# Jukebox.net
KiCad netlist of a schematic drawn in EAGLE
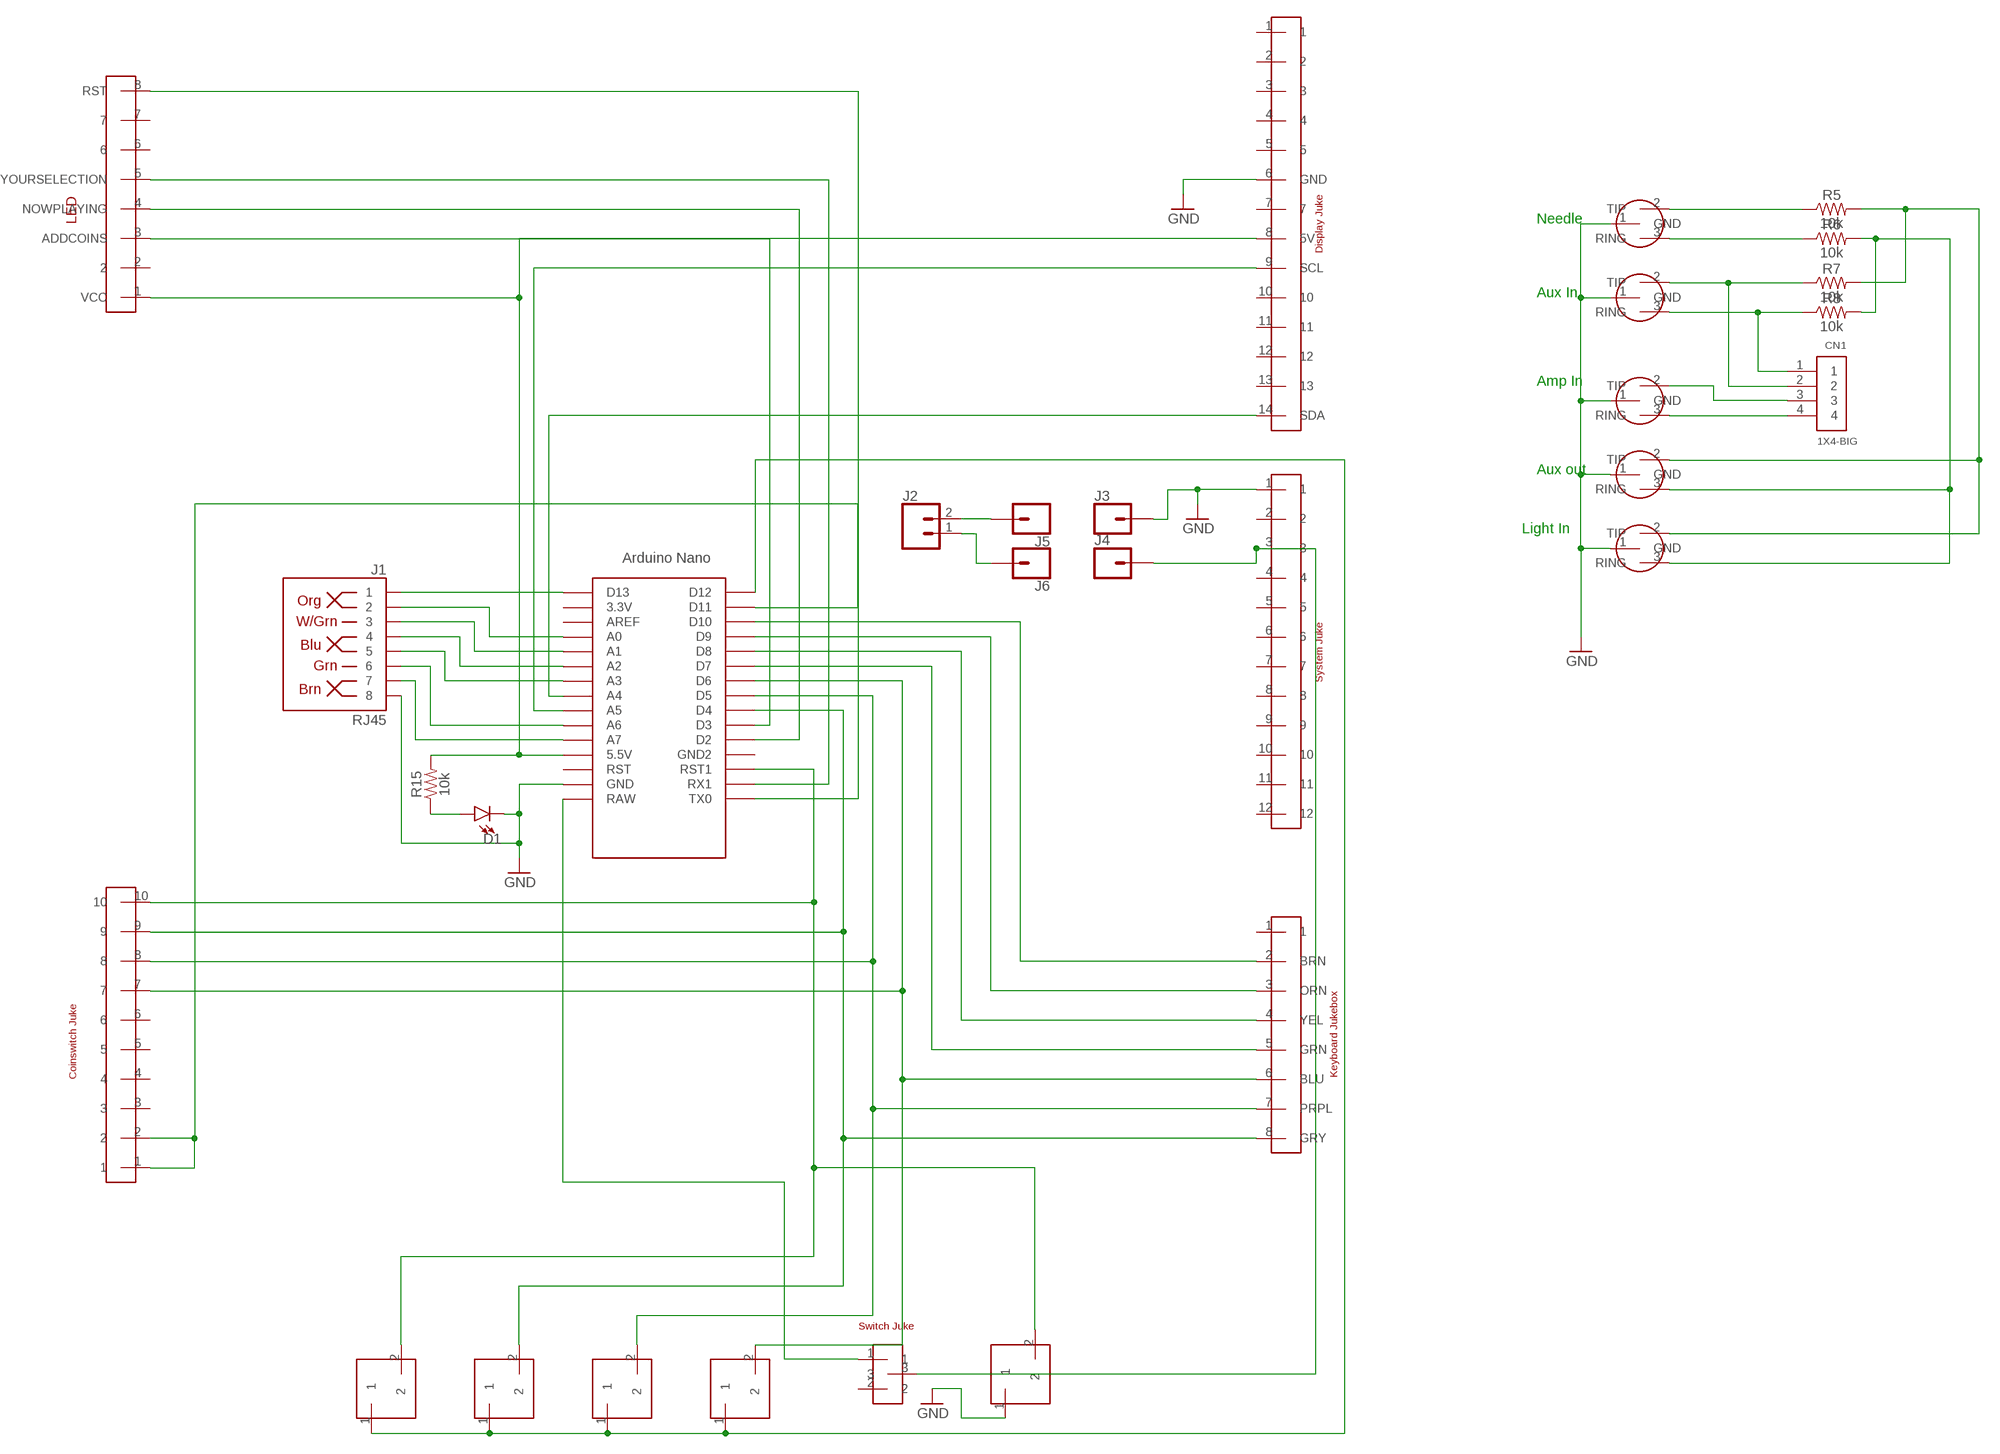
[diagram p0: schematic, sheet 1]

(export (version "E")
  (design (tool "Eeschema 10.0.6"))
  (components
    (comp (ref "CN1")
      (value "1X4-BIG")
      (footprint "eagle-import:1X04-BIG")
      (libsource (lib "eagle-import") (part "1X4-BIG"))
    )
    (comp (ref "D1")
      (value "LED5MM")
      (footprint "eagle-import:LED_5MM")
      (libsource (lib "eagle-import") (part "LED5MM"))
    )
    (comp (ref "J1")
      (value "RJ45")
      (footprint "eagle-import:RJ45-8")
      (libsource (lib "eagle-import") (part "RJ45-8"))
    )
    (comp (ref "J2")
      (value "CONN_02")
      (footprint "eagle-import:1X02")
      (libsource (lib "eagle-import") (part "CONN_02"))
    )
    (comp (ref "J3")
      (value "CONN_01")
      (footprint "eagle-import:1X01")
      (libsource (lib "eagle-import") (part "CONN_01"))
    )
    (comp (ref "J4")
      (value "CONN_01")
      (footprint "eagle-import:1X01")
      (libsource (lib "eagle-import") (part "CONN_01"))
    )
    (comp (ref "J5")
      (value "CONN_01")
      (footprint "eagle-import:1X01")
      (libsource (lib "eagle-import") (part "CONN_01"))
    )
    (comp (ref "J6")
      (value "CONN_01")
      (footprint "eagle-import:1X01")
      (libsource (lib "eagle-import") (part "CONN_01"))
    )
    (comp (ref "R5")
      (value "10k")
      (footprint "eagle-import:AXIAL-0.3")
      (libsource (lib "eagle-import") (part "10KOHM-HORIZ-1/4W-1%"))
    )
    (comp (ref "R6")
      (value "10k")
      (footprint "eagle-import:AXIAL-0.3")
      (libsource (lib "eagle-import") (part "10KOHM-HORIZ-1/4W-1%"))
    )
    (comp (ref "R7")
      (value "10k")
      (footprint "eagle-import:AXIAL-0.3")
      (libsource (lib "eagle-import") (part "10KOHM-HORIZ-1/4W-1%"))
    )
    (comp (ref "R8")
      (value "10k")
      (footprint "eagle-import:AXIAL-0.3")
      (libsource (lib "eagle-import") (part "10KOHM-HORIZ-1/4W-1%"))
    )
    (comp (ref "R15")
      (value "10k")
      (footprint "eagle-import:AXIAL-0.3")
      (libsource (lib "eagle-import") (part "10KOHM-HORIZ-1/4W-1%"))
    )
    (comp (ref "U$1")
      (value "NANO")
      (footprint "eagle-import:NANO")
      (libsource (lib "eagle-import") (part "NANO"))
    )
    (comp (ref "U$2")
      (value "JUKEHEADPHONE")
      (footprint "eagle-import:JUKEHEADPHONE")
      (libsource (lib "eagle-import") (part "JUKEHEADPHONE"))
    )
    (comp (ref "U$3")
      (value "JUKEHEADPHONE")
      (footprint "eagle-import:JUKEHEADPHONE")
      (libsource (lib "eagle-import") (part "JUKEHEADPHONE"))
    )
    (comp (ref "U$4")
      (value "JUKEHEADPHONE")
      (footprint "eagle-import:JUKEHEADPHONE")
      (libsource (lib "eagle-import") (part "JUKEHEADPHONE"))
    )
    (comp (ref "U$5")
      (value "10PINJUKE")
      (footprint "eagle-import:10PINJUKE")
      (libsource (lib "eagle-import") (part "10PINJUKE"))
    )
    (comp (ref "U$6")
      (value "8PINJUKE")
      (footprint "eagle-import:8PINJUKE")
      (libsource (lib "eagle-import") (part "8PINJUKE"))
    )
    (comp (ref "U$7")
      (value "14PINJUKE")
      (footprint "eagle-import:14PINJUKE")
      (libsource (lib "eagle-import") (part "14PINJUKE"))
    )
    (comp (ref "U$8")
      (value "12PINJUKE")
      (footprint "eagle-import:12PINJUKE")
      (libsource (lib "eagle-import") (part "12PINJUKE"))
    )
    (comp (ref "U$9")
      (value "JUKEBUTTON")
      (footprint "eagle-import:JUKEBUTTON")
      (libsource (lib "eagle-import") (part "JUKEBUTTON"))
    )
    (comp (ref "U$10")
      (value "JUKEBUTTON")
      (footprint "eagle-import:JUKEBUTTON")
      (libsource (lib "eagle-import") (part "JUKEBUTTON"))
    )
    (comp (ref "U$11")
      (value "JUKEBUTTON")
      (footprint "eagle-import:JUKEBUTTON")
      (libsource (lib "eagle-import") (part "JUKEBUTTON"))
    )
    (comp (ref "U$12")
      (value "JUKEBUTTON")
      (footprint "eagle-import:JUKEBUTTON")
      (libsource (lib "eagle-import") (part "JUKEBUTTON"))
    )
    (comp (ref "U$13")
      (value "JUKEBUTTON")
      (footprint "eagle-import:JUKEBUTTON")
      (libsource (lib "eagle-import") (part "JUKEBUTTON"))
    )
    (comp (ref "U$14")
      (value "JUKESWITCH")
      (footprint "eagle-import:JUKESWITCH")
      (libsource (lib "eagle-import") (part "JUKESWITCH"))
    )
    (comp (ref "U$15")
      (value "JUKEHEADPHONE")
      (footprint "eagle-import:JUKEHEADPHONE")
      (libsource (lib "eagle-import") (part "JUKEHEADPHONE"))
    )
    (comp (ref "U$16")
      (value "JUKEHEADPHONE")
      (footprint "eagle-import:JUKEHEADPHONE")
      (libsource (lib "eagle-import") (part "JUKEHEADPHONE"))
    )
    (comp (ref "U$17")
      (value "8PINJUKE2")
      (footprint "eagle-import:8PINJUKE")
      (libsource (lib "eagle-import") (part "8PINJUKE2"))
    )
  )
  (nets
    (net (code "1") (name "GND") (class "Default")
      (node (ref "D1") (pin "K") (pinfunction "C_K") (pintype "passive"))
      (node (ref "J1") (pin "8") (pinfunction "8_8") (pintype "bidirectional"))
      (node (ref "J3") (pin "1") (pinfunction "1_1") (pintype "passive"))
      (node (ref "U$1") (pin "GND") (pinfunction "GND_GND") (pintype "bidirectional"))
      (node (ref "U$13") (pin "1") (pinfunction "1_1") (pintype "bidirectional"))
      (node (ref "U$15") (pin "1") (pinfunction "GND_1") (pintype "bidirectional"))
      (node (ref "U$16") (pin "1") (pinfunction "GND_1") (pintype "bidirectional"))
      (node (ref "U$2") (pin "1") (pinfunction "GND_1") (pintype "bidirectional"))
      (node (ref "U$3") (pin "1") (pinfunction "GND_1") (pintype "bidirectional"))
      (node (ref "U$4") (pin "1") (pinfunction "GND_1") (pintype "bidirectional"))
      (node (ref "U$7") (pin "6") (pinfunction "GND_6") (pintype "bidirectional"))
      (node (ref "U$8") (pin "1") (pinfunction "1_1") (pintype "bidirectional"))
    )
    (net (code "2") (name "Net-(J1-Pad1)") (class "Default")
      (node (ref "J1") (pin "1") (pinfunction "1_1") (pintype "bidirectional"))
      (node (ref "U$1") (pin "D13") (pinfunction "D13_D13") (pintype "bidirectional"))
    )
    (net (code "3") (name "Net-(J1-Pad2)") (class "Default")
      (node (ref "J1") (pin "2") (pinfunction "2_2") (pintype "bidirectional"))
      (node (ref "U$1") (pin "A0") (pinfunction "A0_A0") (pintype "bidirectional"))
    )
    (net (code "4") (name "Net-(J1-Pad3)") (class "Default")
      (node (ref "J1") (pin "3") (pinfunction "3_3") (pintype "bidirectional"))
      (node (ref "U$1") (pin "A1") (pinfunction "A1_A1") (pintype "bidirectional"))
    )
    (net (code "5") (name "Net-(J1-Pad4)") (class "Default")
      (node (ref "J1") (pin "4") (pinfunction "4_4") (pintype "bidirectional"))
      (node (ref "U$1") (pin "A2") (pinfunction "A2_A2") (pintype "bidirectional"))
    )
    (net (code "6") (name "Net-(J1-Pad5)") (class "Default")
      (node (ref "J1") (pin "5") (pinfunction "5_5") (pintype "bidirectional"))
      (node (ref "U$1") (pin "A3") (pinfunction "A3_A3") (pintype "bidirectional"))
    )
    (net (code "7") (name "Net-(J1-Pad6)") (class "Default")
      (node (ref "J1") (pin "6") (pinfunction "6_6") (pintype "bidirectional"))
      (node (ref "U$1") (pin "A6") (pinfunction "A6_A6") (pintype "bidirectional"))
    )
    (net (code "8") (name "Net-(J1-Pad7)") (class "Default")
      (node (ref "J1") (pin "7") (pinfunction "7_7") (pintype "bidirectional"))
      (node (ref "U$1") (pin "A7") (pinfunction "A7_A7") (pintype "bidirectional"))
    )
    (net (code "9") (name "Net-(J2-Pad1)") (class "Default")
      (node (ref "J2") (pin "1") (pinfunction "1_1") (pintype "passive"))
      (node (ref "J6") (pin "1") (pinfunction "1_1") (pintype "passive"))
    )
    (net (code "10") (name "Net-(J2-Pad2)") (class "Default")
      (node (ref "J2") (pin "2") (pinfunction "2_2") (pintype "passive"))
      (node (ref "J5") (pin "1") (pinfunction "1_1") (pintype "passive"))
    )
    (net (code "11") (name "Net-(J4-Pad1)") (class "Default")
      (node (ref "J4") (pin "1") (pinfunction "1_1") (pintype "passive"))
      (node (ref "U$14") (pin "3") (pinfunction "3_3") (pintype "bidirectional"))
      (node (ref "U$8") (pin "3") (pinfunction "3_3") (pintype "bidirectional"))
    )
    (net (code "12") (name "Net-(R5-1)") (class "Default")
      (node (ref "R5") (pin "P$1") (pinfunction "1_P$1") (pintype "passive"))
      (node (ref "U$3") (pin "2") (pinfunction "TIP_2") (pintype "bidirectional"))
    )
    (net (code "13") (name "Net-(R5-2)") (class "Default")
      (node (ref "R5") (pin "P$2") (pinfunction "2_P$2") (pintype "passive"))
      (node (ref "R7") (pin "P$2") (pinfunction "2_P$2") (pintype "passive"))
      (node (ref "U$16") (pin "2") (pinfunction "TIP_2") (pintype "bidirectional"))
      (node (ref "U$2") (pin "2") (pinfunction "TIP_2") (pintype "bidirectional"))
    )
    (net (code "14") (name "Net-(R6-1)") (class "Default")
      (node (ref "R6") (pin "P$1") (pinfunction "1_P$1") (pintype "passive"))
      (node (ref "U$3") (pin "3") (pinfunction "RING_3") (pintype "bidirectional"))
    )
    (net (code "15") (name "Net-(R6-2)") (class "Default")
      (node (ref "R6") (pin "P$2") (pinfunction "2_P$2") (pintype "passive"))
      (node (ref "R8") (pin "P$2") (pinfunction "2_P$2") (pintype "passive"))
      (node (ref "U$16") (pin "3") (pinfunction "RING_3") (pintype "bidirectional"))
      (node (ref "U$2") (pin "3") (pinfunction "RING_3") (pintype "bidirectional"))
    )
    (net (code "16") (name "Net-(R7-1)") (class "Default")
      (node (ref "CN1") (pin "2") (pinfunction "2_2") (pintype "bidirectional"))
      (node (ref "R7") (pin "P$1") (pinfunction "1_P$1") (pintype "passive"))
      (node (ref "U$4") (pin "2") (pinfunction "TIP_2") (pintype "bidirectional"))
    )
    (net (code "17") (name "Net-(R8-1)") (class "Default")
      (node (ref "CN1") (pin "1") (pinfunction "1_1") (pintype "bidirectional"))
      (node (ref "R8") (pin "P$1") (pinfunction "1_P$1") (pintype "passive"))
      (node (ref "U$4") (pin "3") (pinfunction "RING_3") (pintype "bidirectional"))
    )
    (net (code "18") (name "Net-(R15-1)") (class "Default")
      (node (ref "D1") (pin "A") (pinfunction "A_A") (pintype "passive"))
      (node (ref "R15") (pin "P$1") (pinfunction "1_P$1") (pintype "passive"))
    )
    (net (code "19") (name "Net-(R15-2)") (class "Default")
      (node (ref "R15") (pin "P$2") (pinfunction "2_P$2") (pintype "passive"))
      (node (ref "U$1") (pin "5V") (pinfunction "5.5V_5V") (pintype "bidirectional"))
      (node (ref "U$17") (pin "1") (pinfunction "VCC_1") (pintype "bidirectional"))
      (node (ref "U$7") (pin "8") (pinfunction "5V_8") (pintype "bidirectional"))
    )
    (net (code "20") (name "Net-(U$1-PadD11)") (class "Default")
      (node (ref "U$1") (pin "D11") (pinfunction "D11_D11") (pintype "bidirectional"))
      (node (ref "U$5") (pin "1") (pinfunction "1_1") (pintype "bidirectional"))
      (node (ref "U$5") (pin "2") (pinfunction "2_2") (pintype "bidirectional"))
    )
    (net (code "21") (name "Net-(U$1-PadD12)") (class "Default")
      (node (ref "U$1") (pin "D12") (pinfunction "D12_D12") (pintype "bidirectional"))
      (node (ref "U$10") (pin "1") (pinfunction "1_1") (pintype "bidirectional"))
      (node (ref "U$11") (pin "1") (pinfunction "1_1") (pintype "bidirectional"))
      (node (ref "U$12") (pin "1") (pinfunction "1_1") (pintype "bidirectional"))
      (node (ref "U$9") (pin "1") (pinfunction "1_1") (pintype "bidirectional"))
    )
    (net (code "22") (name "Net-(U$1-PadRAW)") (class "Default")
      (node (ref "U$1") (pin "RAW") (pinfunction "RAW_RAW") (pintype "bidirectional"))
      (node (ref "U$14") (pin "1") (pinfunction "1_1") (pintype "bidirectional"))
    )
    (net (code "23") (name "Net-(U$1-PadRST1)") (class "Default")
      (node (ref "U$1") (pin "RST1") (pinfunction "RST1_RST1") (pintype "bidirectional"))
      (node (ref "U$13") (pin "2") (pinfunction "2_2") (pintype "bidirectional"))
      (node (ref "U$5") (pin "10") (pinfunction "10_10") (pintype "bidirectional"))
      (node (ref "U$9") (pin "2") (pinfunction "2_2") (pintype "bidirectional"))
    )
    (net (code "24") (name "Net-(U$6-BLU)") (class "Default")
      (node (ref "U$1") (pin "D6") (pinfunction "D6_D6") (pintype "bidirectional"))
      (node (ref "U$12") (pin "2") (pinfunction "2_2") (pintype "bidirectional"))
      (node (ref "U$5") (pin "7") (pinfunction "7_7") (pintype "bidirectional"))
      (node (ref "U$6") (pin "6") (pinfunction "BLU_6") (pintype "bidirectional"))
    )
    (net (code "25") (name "Net-(U$6-BRN)") (class "Default")
      (node (ref "U$1") (pin "D10") (pinfunction "D10_D10") (pintype "bidirectional"))
      (node (ref "U$6") (pin "2") (pinfunction "BRN_2") (pintype "bidirectional"))
    )
    (net (code "26") (name "Net-(U$6-GRN)") (class "Default")
      (node (ref "U$1") (pin "D7") (pinfunction "D7_D7") (pintype "bidirectional"))
      (node (ref "U$6") (pin "5") (pinfunction "GRN_5") (pintype "bidirectional"))
    )
    (net (code "27") (name "Net-(U$6-GRY)") (class "Default")
      (node (ref "U$1") (pin "D4") (pinfunction "D4_D4") (pintype "bidirectional"))
      (node (ref "U$10") (pin "2") (pinfunction "2_2") (pintype "bidirectional"))
      (node (ref "U$5") (pin "9") (pinfunction "9_9") (pintype "bidirectional"))
      (node (ref "U$6") (pin "8") (pinfunction "GRY_8") (pintype "bidirectional"))
    )
    (net (code "28") (name "Net-(U$6-ORN)") (class "Default")
      (node (ref "U$1") (pin "D9") (pinfunction "D9_D9") (pintype "bidirectional"))
      (node (ref "U$6") (pin "3") (pinfunction "ORN_3") (pintype "bidirectional"))
    )
    (net (code "29") (name "Net-(U$6-PRPL)") (class "Default")
      (node (ref "U$1") (pin "D5") (pinfunction "D5_D5") (pintype "bidirectional"))
      (node (ref "U$11") (pin "2") (pinfunction "2_2") (pintype "bidirectional"))
      (node (ref "U$5") (pin "8") (pinfunction "8_8") (pintype "bidirectional"))
      (node (ref "U$6") (pin "7") (pinfunction "PRPL_7") (pintype "bidirectional"))
    )
    (net (code "30") (name "Net-(U$6-YEL)") (class "Default")
      (node (ref "U$1") (pin "D8") (pinfunction "D8_D8") (pintype "bidirectional"))
      (node (ref "U$6") (pin "4") (pinfunction "YEL_4") (pintype "bidirectional"))
    )
    (net (code "31") (name "Net-(U$7-SCL)") (class "Default")
      (node (ref "U$1") (pin "A5") (pinfunction "A5_A5") (pintype "bidirectional"))
      (node (ref "U$7") (pin "9") (pinfunction "SCL_9") (pintype "bidirectional"))
    )
    (net (code "32") (name "Net-(U$7-SDA)") (class "Default")
      (node (ref "U$1") (pin "A4") (pinfunction "A4_A4") (pintype "bidirectional"))
      (node (ref "U$7") (pin "14") (pinfunction "SDA_14") (pintype "bidirectional"))
    )
    (net (code "33") (name "Net-(U$15-RING)") (class "Default")
      (node (ref "CN1") (pin "4") (pinfunction "4_4") (pintype "bidirectional"))
      (node (ref "U$15") (pin "3") (pinfunction "RING_3") (pintype "bidirectional"))
    )
    (net (code "34") (name "Net-(U$15-TIP)") (class "Default")
      (node (ref "CN1") (pin "3") (pinfunction "3_3") (pintype "bidirectional"))
      (node (ref "U$15") (pin "2") (pinfunction "TIP_2") (pintype "bidirectional"))
    )
    (net (code "35") (name "Net-(U$17-ADDCOINS)") (class "Default")
      (node (ref "U$1") (pin "D3") (pinfunction "D3_D3") (pintype "bidirectional"))
      (node (ref "U$17") (pin "3") (pinfunction "ADDCOINS_3") (pintype "bidirectional"))
    )
    (net (code "36") (name "Net-(U$17-NOWPLAYING)") (class "Default")
      (node (ref "U$1") (pin "D2") (pinfunction "D2_D2") (pintype "bidirectional"))
      (node (ref "U$17") (pin "4") (pinfunction "NOWPLAYING_4") (pintype "bidirectional"))
    )
    (net (code "37") (name "Net-(U$17-RST)") (class "Default")
      (node (ref "U$1") (pin "TX0") (pinfunction "TX0_TX0") (pintype "bidirectional"))
      (node (ref "U$17") (pin "8") (pinfunction "RST_8") (pintype "bidirectional"))
    )
    (net (code "38") (name "Net-(U$17-YOURSELECTION)") (class "Default")
      (node (ref "U$1") (pin "RX1") (pinfunction "RX1_RX1") (pintype "bidirectional"))
      (node (ref "U$17") (pin "5") (pinfunction "YOURSELECTION_5") (pintype "bidirectional"))
    )
    (net (code "39") (name "unconnected-(U$1-GND2-PadGND1)") (class "Default")
      (node (ref "U$1") (pin "GND1") (pinfunction "GND2_GND1") (pintype "bidirectional"))
    )
    (net (code "40") (name "unconnected-(U$1-Pad3.3V)") (class "Default")
      (node (ref "U$1") (pin "3.3V") (pinfunction "3.3V_3.3V") (pintype "bidirectional"))
    )
    (net (code "41") (name "unconnected-(U$1-PadAREF)") (class "Default")
      (node (ref "U$1") (pin "AREF") (pinfunction "AREF_AREF") (pintype "bidirectional"))
    )
    (net (code "42") (name "unconnected-(U$1-PadICSP1)") (class "Default")
      (node (ref "U$1") (pin "ICSP1") (pinfunction "ICSP1_ICSP1") (pintype "bidirectional"))
    )
    (net (code "43") (name "unconnected-(U$1-PadICSP2)") (class "Default")
      (node (ref "U$1") (pin "ICSP2") (pinfunction "ICSP2_ICSP2") (pintype "bidirectional"))
    )
    (net (code "44") (name "unconnected-(U$1-PadICSP3)") (class "Default")
      (node (ref "U$1") (pin "ICSP3") (pinfunction "ICSP3_ICSP3") (pintype "bidirectional"))
    )
    (net (code "45") (name "unconnected-(U$1-PadICSP4)") (class "Default")
      (node (ref "U$1") (pin "ICSP4") (pinfunction "ICSP4_ICSP4") (pintype "bidirectional"))
    )
    (net (code "46") (name "unconnected-(U$1-PadICSP5)") (class "Default")
      (node (ref "U$1") (pin "ICSP5") (pinfunction "ICSP5_ICSP5") (pintype "bidirectional"))
    )
    (net (code "47") (name "unconnected-(U$1-PadICSP6)") (class "Default")
      (node (ref "U$1") (pin "ICSP6") (pinfunction "ICSP6_ICSP6") (pintype "bidirectional"))
    )
    (net (code "48") (name "unconnected-(U$1-PadRST)") (class "Default")
      (node (ref "U$1") (pin "RST") (pinfunction "RST_RST") (pintype "bidirectional"))
    )
    (net (code "49") (name "unconnected-(U$5-Pad3)") (class "Default")
      (node (ref "U$5") (pin "3") (pinfunction "3_3") (pintype "bidirectional"))
    )
    (net (code "50") (name "unconnected-(U$5-Pad4)") (class "Default")
      (node (ref "U$5") (pin "4") (pinfunction "4_4") (pintype "bidirectional"))
    )
    (net (code "51") (name "unconnected-(U$5-Pad5)") (class "Default")
      (node (ref "U$5") (pin "5") (pinfunction "5_5") (pintype "bidirectional"))
    )
    (net (code "52") (name "unconnected-(U$5-Pad6)") (class "Default")
      (node (ref "U$5") (pin "6") (pinfunction "6_6") (pintype "bidirectional"))
    )
    (net (code "53") (name "unconnected-(U$6-Pad1)") (class "Default")
      (node (ref "U$6") (pin "1") (pinfunction "1_1") (pintype "bidirectional"))
    )
    (net (code "54") (name "unconnected-(U$7-Pad1)") (class "Default")
      (node (ref "U$7") (pin "1") (pinfunction "1_1") (pintype "bidirectional"))
    )
    (net (code "55") (name "unconnected-(U$7-Pad2)") (class "Default")
      (node (ref "U$7") (pin "2") (pinfunction "2_2") (pintype "bidirectional"))
    )
    (net (code "56") (name "unconnected-(U$7-Pad3)") (class "Default")
      (node (ref "U$7") (pin "3") (pinfunction "3_3") (pintype "bidirectional"))
    )
    (net (code "57") (name "unconnected-(U$7-Pad4)") (class "Default")
      (node (ref "U$7") (pin "4") (pinfunction "4_4") (pintype "bidirectional"))
    )
    (net (code "58") (name "unconnected-(U$7-Pad5)") (class "Default")
      (node (ref "U$7") (pin "5") (pinfunction "5_5") (pintype "bidirectional"))
    )
    (net (code "59") (name "unconnected-(U$7-Pad7)") (class "Default")
      (node (ref "U$7") (pin "7") (pinfunction "7_7") (pintype "bidirectional"))
    )
    (net (code "60") (name "unconnected-(U$7-Pad10)") (class "Default")
      (node (ref "U$7") (pin "10") (pinfunction "10_10") (pintype "bidirectional"))
    )
    (net (code "61") (name "unconnected-(U$7-Pad11)") (class "Default")
      (node (ref "U$7") (pin "11") (pinfunction "11_11") (pintype "bidirectional"))
    )
    (net (code "62") (name "unconnected-(U$7-Pad12)") (class "Default")
      (node (ref "U$7") (pin "12") (pinfunction "12_12") (pintype "bidirectional"))
    )
    (net (code "63") (name "unconnected-(U$7-Pad13)") (class "Default")
      (node (ref "U$7") (pin "13") (pinfunction "13_13") (pintype "bidirectional"))
    )
    (net (code "64") (name "unconnected-(U$8-Pad2)") (class "Default")
      (node (ref "U$8") (pin "2") (pinfunction "2_2") (pintype "bidirectional"))
    )
    (net (code "65") (name "unconnected-(U$8-Pad4)") (class "Default")
      (node (ref "U$8") (pin "4") (pinfunction "4_4") (pintype "bidirectional"))
    )
    (net (code "66") (name "unconnected-(U$8-Pad5)") (class "Default")
      (node (ref "U$8") (pin "5") (pinfunction "5_5") (pintype "bidirectional"))
    )
    (net (code "67") (name "unconnected-(U$8-Pad6)") (class "Default")
      (node (ref "U$8") (pin "6") (pinfunction "6_6") (pintype "bidirectional"))
    )
    (net (code "68") (name "unconnected-(U$8-Pad7)") (class "Default")
      (node (ref "U$8") (pin "7") (pinfunction "7_7") (pintype "bidirectional"))
    )
    (net (code "69") (name "unconnected-(U$8-Pad8)") (class "Default")
      (node (ref "U$8") (pin "8") (pinfunction "8_8") (pintype "bidirectional"))
    )
    (net (code "70") (name "unconnected-(U$8-Pad9)") (class "Default")
      (node (ref "U$8") (pin "9") (pinfunction "9_9") (pintype "bidirectional"))
    )
    (net (code "71") (name "unconnected-(U$8-Pad10)") (class "Default")
      (node (ref "U$8") (pin "10") (pinfunction "10_10") (pintype "bidirectional"))
    )
    (net (code "72") (name "unconnected-(U$8-Pad11)") (class "Default")
      (node (ref "U$8") (pin "11") (pinfunction "11_11") (pintype "bidirectional"))
    )
    (net (code "73") (name "unconnected-(U$8-Pad12)") (class "Default")
      (node (ref "U$8") (pin "12") (pinfunction "12_12") (pintype "bidirectional"))
    )
    (net (code "74") (name "unconnected-(U$14-Pad2)") (class "Default")
      (node (ref "U$14") (pin "2") (pinfunction "2_2") (pintype "bidirectional"))
    )
    (net (code "75") (name "unconnected-(U$17-Pad2)") (class "Default")
      (node (ref "U$17") (pin "2") (pinfunction "2_2") (pintype "bidirectional"))
    )
    (net (code "76") (name "unconnected-(U$17-Pad6)") (class "Default")
      (node (ref "U$17") (pin "6") (pinfunction "6_6") (pintype "bidirectional"))
    )
    (net (code "77") (name "unconnected-(U$17-Pad7)") (class "Default")
      (node (ref "U$17") (pin "7") (pinfunction "7_7") (pintype "bidirectional"))
    )
  )
)
